# AUC3.net
KiCad netlist of a schematic drawn in Altium Designer
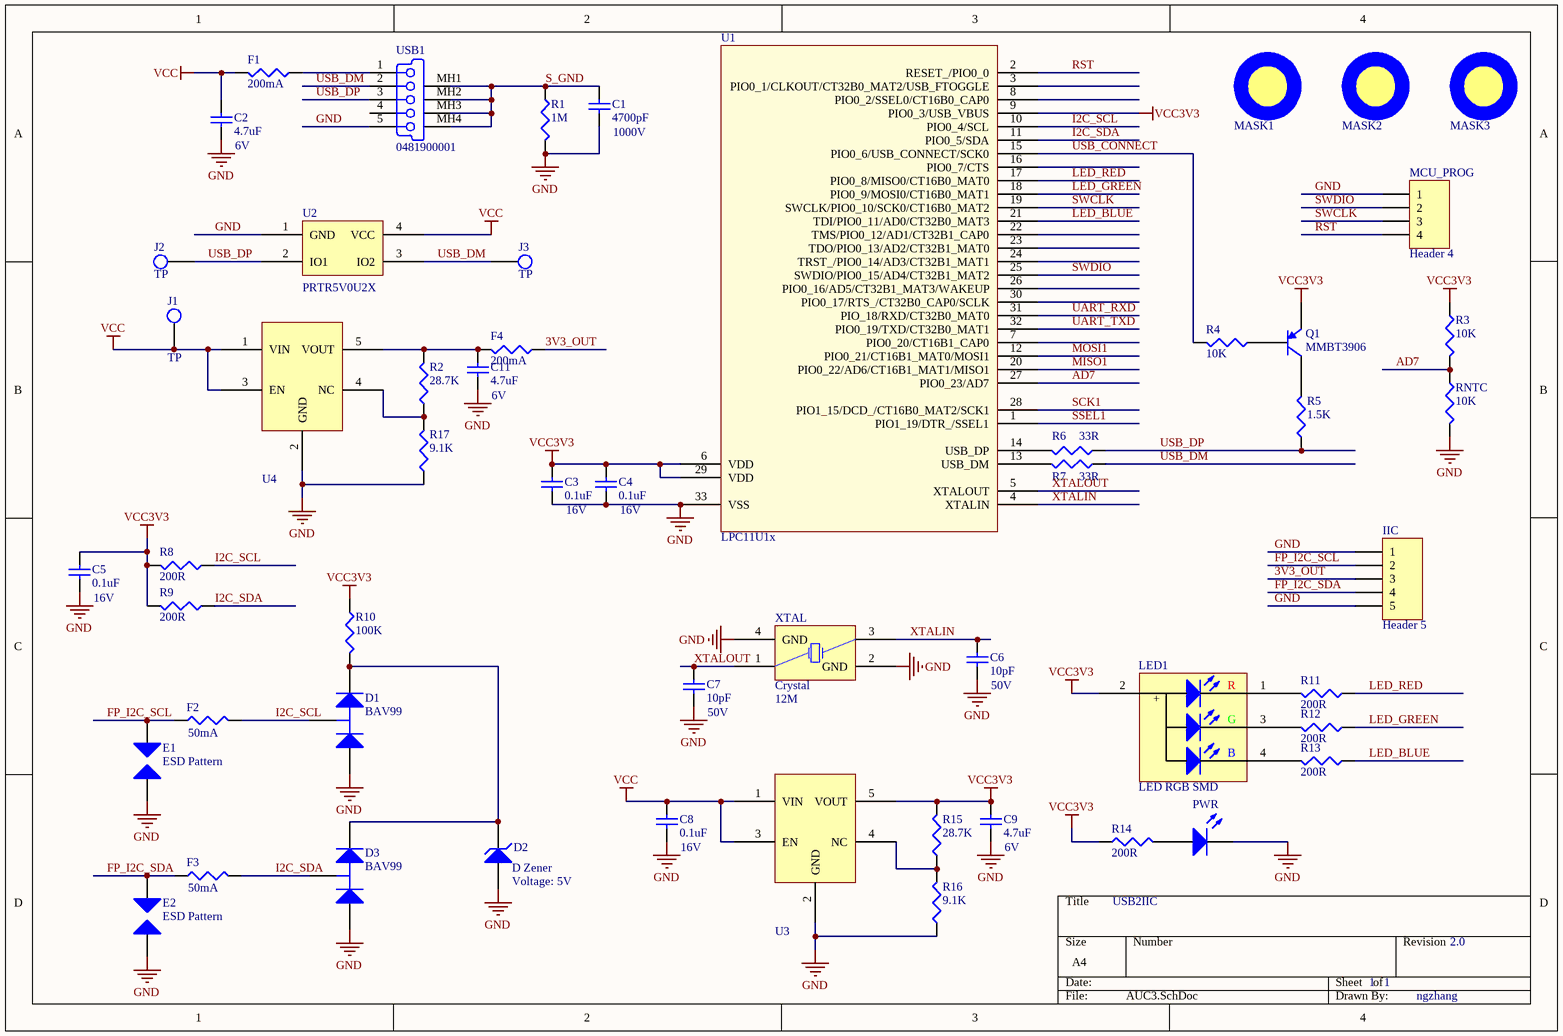
[diagram p0: AUC3.SchDoc]

(export (version "E")
  (design (tool "Eeschema 10.0.6"))
  (components
    (comp (ref "C1")
      (value "4700pF")
      (footprint "CAPC3216L")
      (description "Capacitor (Semiconductor SIM Model)")
      (fields (field (name "VOLTAGE") "1000V") (field (name "PUBLISHER") "Altium Limited"))
      (libsource (lib "avalon_all") (part "Cap Semi"))
    )
    (comp (ref "C2")
      (value "4.7uF")
      (footprint "CAPC1608L")
      (description "Capacitor (Semiconductor SIM Model)")
      (fields (field (name "VOLTAGE") "6V") (field (name "PUBLISHER") "Altium Limited"))
      (libsource (lib "Miscellaneous Devices") (part "Cap Semi"))
    )
    (comp (ref "C3")
      (value "0.1uF")
      (footprint "CAPC1005L")
      (description "Capacitor (Semiconductor SIM Model)")
      (fields (field (name "VOLTAGE") "16V") (field (name "PUBLISHER") "Altium Limited"))
      (libsource (lib "Miscellaneous Devices") (part "Cap Semi"))
    )
    (comp (ref "C4")
      (value "0.1uF")
      (footprint "CAPC1005L")
      (description "Capacitor (Semiconductor SIM Model)")
      (fields (field (name "VOLTAGE") "16V") (field (name "PUBLISHER") "Altium Limited"))
      (libsource (lib "Miscellaneous Devices") (part "Cap Semi"))
    )
    (comp (ref "C5")
      (value "0.1uF")
      (footprint "CAPC1005L")
      (description "Capacitor (Semiconductor SIM Model)")
      (fields (field (name "VOLTAGE") "16V") (field (name "PUBLISHER") "Altium Limited"))
      (libsource (lib "Miscellaneous Devices") (part "Cap Semi"))
    )
    (comp (ref "C6")
      (value "10pF")
      (footprint "CAPC1005L")
      (description "Capacitor (Semiconductor SIM Model)")
      (fields (field (name "VOLTAGE") "50V") (field (name "PUBLISHER") "Altium Limited"))
      (libsource (lib "Miscellaneous Devices") (part "Cap Semi"))
    )
    (comp (ref "C7")
      (value "10pF")
      (footprint "CAPC1005L")
      (description "Capacitor (Semiconductor SIM Model)")
      (fields (field (name "VOLTAGE") "50V") (field (name "PUBLISHER") "Altium Limited"))
      (libsource (lib "Miscellaneous Devices") (part "Cap Semi"))
    )
    (comp (ref "C8")
      (value "0.1uF")
      (footprint "CAPC1005L")
      (description "Capacitor (Semiconductor SIM Model)")
      (fields (field (name "VOLTAGE") "16V") (field (name "PUBLISHER") "Altium Limited"))
      (libsource (lib "Miscellaneous Devices") (part "Cap Semi"))
    )
    (comp (ref "C9")
      (value "4.7uF")
      (footprint "CAPC1608L")
      (description "Capacitor (Semiconductor SIM Model)")
      (fields (field (name "VOLTAGE") "6V") (field (name "PUBLISHER") "Altium Limited"))
      (libsource (lib "Miscellaneous Devices") (part "Cap Semi"))
    )
    (comp (ref "C11")
      (value "4.7uF")
      (footprint "CAPC1608L")
      (description "Capacitor (Semiconductor SIM Model)")
      (fields (field (name "VOLTAGE") "6V") (field (name "PUBLISHER") "Altium Limited"))
      (libsource (lib "Miscellaneous Devices") (part "Cap Semi"))
    )
    (comp (ref "D1")
      (value "BAV99")
      (footprint "SOT-23_L")
      (description "Silicon Switching Diode Array for High-Speed Switching")
      (fields (field (name "PUBLISHER") "Altium Limited"))
      (libsource (lib "Infineon Discrete Diode") (part "BAV99"))
    )
    (comp (ref "D2")
      (value "D Zener")
      (footprint "DO-214AC")
      (description "Zener Diode")
      (fields (field (name "VOLTAGE") "5V") (field (name "PUBLISHER") "Altium Limited"))
      (libsource (lib "Miscellaneous Devices") (part "D Zener"))
    )
    (comp (ref "D3")
      (value "BAV99")
      (footprint "SOT-23_L")
      (description "Silicon Switching Diode Array for High-Speed Switching")
      (fields (field (name "PUBLISHER") "Altium Limited"))
      (libsource (lib "Infineon Discrete Diode") (part "BAV99"))
    )
    (comp (ref "E1") (value "ESD Pattern") (footprint "ESD") (libsource (lib "avalon_all") (part "ESD")))
    (comp (ref "E2") (value "ESD Pattern") (footprint "ESD") (libsource (lib "avalon_all") (part "ESD")))
    (comp (ref "F1")
      (value "200mA")
      (footprint "RESC3216L")
      (description "Resistor")
      (fields (field (name "PUBLISHER") "Altium Limited"))
      (libsource (lib "avalon_all") (part "Res3"))
    )
    (comp (ref "F2")
      (value "50mA")
      (footprint "RESC2012l")
      (description "Resistor")
      (fields (field (name "PUBLISHER") "Altium Limited"))
      (libsource (lib "Miscellaneous Devices") (part "Res3"))
    )
    (comp (ref "F3")
      (value "50mA")
      (footprint "RESC2012l")
      (description "Resistor")
      (fields (field (name "PUBLISHER") "Altium Limited"))
      (libsource (lib "Miscellaneous Devices") (part "Res3"))
    )
    (comp (ref "F4")
      (value "200mA")
      (footprint "RESC3216L")
      (description "Resistor")
      (fields (field (name "PUBLISHER") "Altium Limited"))
      (libsource (lib "avalon_all") (part "Res3"))
    )
    (comp (ref "IIC")
      (value "Header 5")
      (footprint "HDR1X50-s")
      (description "Header, 5-Pin")
      (fields (field (name "PUBLISHER") "Altium Limited"))
      (libsource (lib "Miscellaneous Connectors") (part "Header 5"))
    )
    (comp (ref "J1")
      (value "TP")
      (footprint "tp")
      (fields (field (name "PUBLISHER") "Altium Limited"))
      (libsource (lib "A7.1") (part "TP"))
    )
    (comp (ref "J2")
      (value "TP")
      (footprint "tp")
      (fields (field (name "PUBLISHER") "Altium Limited"))
      (libsource (lib "A7.1") (part "TP"))
    )
    (comp (ref "J3")
      (value "TP")
      (footprint "tp")
      (fields (field (name "PUBLISHER") "Altium Limited"))
      (libsource (lib "A7.1") (part "TP"))
    )
    (comp (ref "LED1")
      (value "LED RGB SMD")
      (footprint "LED3528RGB")
      (libsource (lib "avalon_all") (part "LED3528RGB"))
    )
    (comp (ref "MASK1") (value "MASK") (footprint "MASK_L") (libsource (lib "avalon_all") (part "MASK")))
    (comp (ref "MASK2") (value "MASK") (footprint "MASK_L") (libsource (lib "avalon_all") (part "MASK")))
    (comp (ref "MASK3") (value "MASK") (footprint "MASKTEST") (libsource (lib "avalon_all") (part "MASK")))
    (comp (ref "MCU_PROG")
      (value "Header 4")
      (footprint "HDR1X4")
      (description "Header, 4-Pin")
      (fields (field (name "PUBLISHER") "Altium Limited"))
      (libsource (lib "Miscellaneous Connectors") (part "Header 4"))
    )
    (comp (ref "PWR")
      (value "LED3")
      (footprint "CD1608-0603")
      (description "Typical GREEN SiC LED")
      (fields (field (name "PUBLISHER") "Altium Limited"))
      (libsource (lib "avalon_all") (part "LED3"))
    )
    (comp (ref "Q1")
      (value "MMBT3906")
      (footprint "SOT23_N")
      (description "PNP Switching Transistor")
      (fields (field (name "PUBLISHER") "Altium Limited"))
      (libsource (lib "Philips Discrete BJT - Low Power") (part "MMBT3906"))
    )
    (comp (ref "R1")
      (value "1M")
      (footprint "RESC3216L")
      (description "Resistor")
      (fields (field (name "PUBLISHER") "Altium Limited"))
      (libsource (lib "avalon_all") (part "Res3"))
    )
    (comp (ref "R2")
      (value "28.7K")
      (footprint "RESC1005L")
      (description "Resistor")
      (fields (field (name "PUBLISHER") "Altium Limited"))
      (libsource (lib "avalon_all") (part "Res3"))
    )
    (comp (ref "R3")
      (value "10K")
      (footprint "RESC1005L")
      (description "Resistor")
      (fields (field (name "PUBLISHER") "Altium Limited"))
      (libsource (lib "avalon_all") (part "Res3"))
    )
    (comp (ref "R4")
      (value "10K")
      (footprint "RESC1005L")
      (description "Resistor")
      (fields (field (name "PUBLISHER") "Altium Limited"))
      (libsource (lib "avalon_all") (part "Res3"))
    )
    (comp (ref "R5")
      (value "1.5K")
      (footprint "RESC1005L")
      (description "Resistor")
      (fields (field (name "PUBLISHER") "Altium Limited"))
      (libsource (lib "avalon_all") (part "Res3"))
    )
    (comp (ref "R6")
      (value "33R")
      (footprint "RESC1005L")
      (description "Resistor")
      (fields (field (name "PUBLISHER") "Altium Limited"))
      (libsource (lib "avalon_all") (part "Res3"))
    )
    (comp (ref "R7")
      (value "33R")
      (footprint "RESC1005L")
      (description "Resistor")
      (fields (field (name "PUBLISHER") "Altium Limited"))
      (libsource (lib "avalon_all") (part "Res3"))
    )
    (comp (ref "R8")
      (value "200R")
      (footprint "RESC1005L")
      (description "Resistor")
      (fields (field (name "PUBLISHER") "Altium Limited"))
      (libsource (lib "avalon_all") (part "Res3"))
    )
    (comp (ref "R9")
      (value "200R")
      (footprint "RESC1005L")
      (description "Resistor")
      (fields (field (name "PUBLISHER") "Altium Limited"))
      (libsource (lib "avalon_all") (part "Res3"))
    )
    (comp (ref "R10")
      (value "100K")
      (footprint "RESC1005L")
      (description "Resistor")
      (fields (field (name "PUBLISHER") "Altium Limited"))
      (libsource (lib "avalon_all") (part "Res3"))
    )
    (comp (ref "R11")
      (value "200R")
      (footprint "RESC1005L")
      (description "Resistor")
      (fields (field (name "PUBLISHER") "Altium Limited"))
      (libsource (lib "avalon_all") (part "Res3"))
    )
    (comp (ref "R12")
      (value "200R")
      (footprint "RESC1005L")
      (description "Resistor")
      (fields (field (name "PUBLISHER") "Altium Limited"))
      (libsource (lib "avalon_all") (part "Res3"))
    )
    (comp (ref "R13")
      (value "200R")
      (footprint "RESC1005L")
      (description "Resistor")
      (fields (field (name "PUBLISHER") "Altium Limited"))
      (libsource (lib "avalon_all") (part "Res3"))
    )
    (comp (ref "R14")
      (value "200R")
      (footprint "RESC1005L")
      (description "Resistor")
      (fields (field (name "PUBLISHER") "Altium Limited"))
      (libsource (lib "avalon_all") (part "Res3"))
    )
    (comp (ref "R15")
      (value "28.7K")
      (footprint "RESC1005L")
      (description "Resistor")
      (fields (field (name "PUBLISHER") "Altium Limited"))
      (libsource (lib "avalon_all") (part "Res3"))
    )
    (comp (ref "R16")
      (value "9.1K")
      (footprint "RESC1005L")
      (description "Resistor")
      (fields (field (name "PUBLISHER") "Altium Limited"))
      (libsource (lib "avalon_all") (part "Res3"))
    )
    (comp (ref "R17")
      (value "9.1K")
      (footprint "RESC1005L")
      (description "Resistor")
      (fields (field (name "PUBLISHER") "Altium Limited"))
      (libsource (lib "avalon_all") (part "Res3"))
    )
    (comp (ref "RNTC")
      (value "10K")
      (footprint "RESC1608L")
      (description "Resistor")
      (fields (field (name "PUBLISHER") "Altium Limited"))
      (libsource (lib "avalon_all") (part "Res3"))
    )
    (comp (ref "U1")
      (value "LPC11U1x")
      (footprint "HVQFN33")
      (description "32-bit ARM Cortex-M0 microcontroller")
      (libsource (lib "avalon_all") (part "LPC11U1x"))
    )
    (comp (ref "U2")
      (value "PRTR5V0U2X")
      (footprint "SOT143B_L")
      (description "Ultra low capacitance double rail-to-rail ESD protection diode")
      (libsource (lib "avalon_all") (part "PRTR5V0U2X"))
    )
    (comp (ref "U3")
      (value "LDO")
      (footprint "SOT23-5AL")
      (description "600mA, Ultra-Low Dropout, CMOS Regulatorout Bypass Capacitor CMOS LDO Regulator")
      (libsource (lib "avalon_all") (part "RT9187C"))
    )
    (comp (ref "U4")
      (value "LDO")
      (footprint "SOT23-5AL")
      (description "600mA, Ultra-Low Dropout, CMOS Regulatorout Bypass Capacitor CMOS LDO Regulator")
      (libsource (lib "avalon_all") (part "RT9187C"))
    )
    (comp (ref "USB1")
      (value "0481900001")
      (footprint "USB_Micro_B2")
      (fields (field (name "PUBLISHER") "Altium Limited"))
      (libsource (lib "Molex Serial Bus Mini USB") (part "0481900001"))
    )
    (comp (ref "XTAL")
      (value "Crystal")
      (footprint "XO2520")
      (fields (field (name "ALTIUM_VALUE") "12M"))
      (libsource (lib "avalon_all") (part "Crystal SMD"))
    )
  )
  (nets
    (net (code "1") (name "/3V3_OUT") (class "Default")
      (node (ref "F4") (pin "1") (pinfunction "1_1") (pintype "passive"))
      (node (ref "IIC") (pin "3") (pinfunction "3_3") (pintype "passive"))
    )
    (net (code "2") (name "/AD7") (class "Default")
      (node (ref "R3") (pin "2") (pinfunction "2_2") (pintype "passive"))
      (node (ref "RNTC") (pin "1") (pinfunction "1_1") (pintype "passive"))
      (node (ref "U1") (pin "27") (pinfunction "PIO0_23/AD7_27") (pintype "passive"))
    )
    (net (code "3") (name "/FP_I2C_SCL") (class "Default")
      (node (ref "E1") (pin "2") (pinfunction "2_2") (pintype "passive"))
      (node (ref "F2") (pin "1") (pinfunction "1_1") (pintype "passive"))
      (node (ref "IIC") (pin "2") (pinfunction "2_2") (pintype "passive"))
    )
    (net (code "4") (name "/FP_I2C_SDA") (class "Default")
      (node (ref "E2") (pin "2") (pinfunction "2_2") (pintype "passive"))
      (node (ref "F3") (pin "1") (pinfunction "1_1") (pintype "passive"))
      (node (ref "IIC") (pin "4") (pinfunction "4_4") (pintype "passive"))
    )
    (net (code "5") (name "/I2C_SCL") (class "Default")
      (node (ref "D1") (pin "3") (pinfunction "C_3") (pintype "passive"))
      (node (ref "F2") (pin "2") (pinfunction "2_2") (pintype "passive"))
      (node (ref "R8") (pin "1") (pinfunction "1_1") (pintype "passive"))
      (node (ref "U1") (pin "10") (pinfunction "PIO0_4/SCL_10") (pintype "passive"))
    )
    (net (code "6") (name "/I2C_SDA") (class "Default")
      (node (ref "D3") (pin "3") (pinfunction "C_3") (pintype "passive"))
      (node (ref "F3") (pin "2") (pinfunction "2_2") (pintype "passive"))
      (node (ref "R9") (pin "1") (pinfunction "1_1") (pintype "passive"))
      (node (ref "U1") (pin "11") (pinfunction "PIO0_5/SDA_11") (pintype "passive"))
    )
    (net (code "7") (name "/LED_BLUE") (class "Default")
      (node (ref "R13") (pin "1") (pinfunction "1_1") (pintype "passive"))
      (node (ref "U1") (pin "21") (pinfunction "TDI/PIO0_11/AD0/CT32B0_MAT3_21") (pintype "passive"))
    )
    (net (code "8") (name "/LED_GREEN") (class "Default")
      (node (ref "R12") (pin "1") (pinfunction "1_1") (pintype "passive"))
      (node (ref "U1") (pin "18") (pinfunction "PIO0_9/MOSI0/CT16B0_MAT1_18") (pintype "passive"))
    )
    (net (code "9") (name "/LED_RED") (class "Default")
      (node (ref "R11") (pin "1") (pinfunction "1_1") (pintype "passive"))
      (node (ref "U1") (pin "17") (pinfunction "PIO0_8/MISO0/CT16B0_MAT0_17") (pintype "passive"))
    )
    (net (code "10") (name "/MISO1") (class "Default")
      (node (ref "U1") (pin "20") (pinfunction "PIO0_22/AD6/CT16B1_MAT1/MISO1_20") (pintype "passive"))
    )
    (net (code "11") (name "/MOSI1") (class "Default")
      (node (ref "U1") (pin "12") (pinfunction "PIO0_21/CT16B1_MAT0/MOSI1_12") (pintype "passive"))
    )
    (net (code "12") (name "/RST") (class "Default")
      (node (ref "MCU_PROG") (pin "4") (pinfunction "4_4") (pintype "passive"))
      (node (ref "U1") (pin "2") (pinfunction "RESET_/PIO0_0_2") (pintype "passive"))
    )
    (net (code "13") (name "/SCK1") (class "Default")
      (node (ref "U1") (pin "28") (pinfunction "PIO1_15/DCD_/CT16B0_MAT2/SCK1_28") (pintype "passive"))
    )
    (net (code "14") (name "/SSEL1") (class "Default")
      (node (ref "U1") (pin "1") (pinfunction "PIO1_19/DTR_/SSEL1_1") (pintype "passive"))
    )
    (net (code "15") (name "/SWCLK") (class "Default")
      (node (ref "MCU_PROG") (pin "3") (pinfunction "3_3") (pintype "passive"))
      (node (ref "U1") (pin "19") (pinfunction "SWCLK/PIO0_10/SCK0/CT16B0_MAT2_19") (pintype "passive"))
    )
    (net (code "16") (name "/SWDIO") (class "Default")
      (node (ref "MCU_PROG") (pin "2") (pinfunction "2_2") (pintype "passive"))
      (node (ref "U1") (pin "25") (pinfunction "SWDIO/PIO0_15/AD4/CT32B1_MAT2_25") (pintype "passive"))
    )
    (net (code "17") (name "/S_GND") (class "Default")
      (node (ref "C1") (pin "2") (pinfunction "2_2") (pintype "passive"))
      (node (ref "R1") (pin "1") (pinfunction "1_1") (pintype "passive"))
      (node (ref "USB1") (pin "MH1") (pinfunction "Tab_MH1") (pintype "passive"))
      (node (ref "USB1") (pin "MH2") (pinfunction "Tab_MH2") (pintype "passive"))
      (node (ref "USB1") (pin "MH3") (pinfunction "Tab_MH3") (pintype "passive"))
      (node (ref "USB1") (pin "MH4") (pinfunction "Tab_MH4") (pintype "passive"))
    )
    (net (code "18") (name "/UART_RXD") (class "Default")
      (node (ref "U1") (pin "31") (pinfunction "PIO_18/RXD/CT32B0_MAT0_31") (pintype "passive"))
    )
    (net (code "19") (name "/UART_TXD") (class "Default")
      (node (ref "U1") (pin "32") (pinfunction "PIO0_19/TXD/CT32B0_MAT1_32") (pintype "passive"))
    )
    (net (code "20") (name "/USB_CONNECT") (class "Default")
      (node (ref "R4") (pin "2") (pinfunction "2_2") (pintype "passive"))
      (node (ref "U1") (pin "15") (pinfunction "PIO0_6/USB_CONNECT/SCK0_15") (pintype "passive"))
    )
    (net (code "21") (name "/USB_DM") (class "Default")
      (node (ref "J3") (pin "1") (pinfunction "1_1") (pintype "passive"))
      (node (ref "R7") (pin "1") (pinfunction "1_1") (pintype "passive"))
      (node (ref "U2") (pin "3") (pinfunction "IO2_3") (pintype "power_in"))
      (node (ref "USB1") (pin "2") (pinfunction "D-_2") (pintype "passive"))
    )
    (net (code "22") (name "/USB_DP") (class "Default")
      (node (ref "J2") (pin "1") (pinfunction "1_1") (pintype "passive"))
      (node (ref "R5") (pin "1") (pinfunction "1_1") (pintype "passive"))
      (node (ref "R6") (pin "1") (pinfunction "1_1") (pintype "passive"))
      (node (ref "U2") (pin "2") (pinfunction "IO1_2") (pintype "power_in"))
      (node (ref "USB1") (pin "3") (pinfunction "D+_3") (pintype "passive"))
    )
    (net (code "23") (name "/XTALIN") (class "Default")
      (node (ref "C6") (pin "1") (pinfunction "1_1") (pintype "passive"))
      (node (ref "U1") (pin "4") (pinfunction "XTALIN_4") (pintype "passive"))
      (node (ref "XTAL") (pin "3") (pinfunction "OSC2_3") (pintype "passive"))
    )
    (net (code "24") (name "/XTALOUT") (class "Default")
      (node (ref "C7") (pin "1") (pinfunction "1_1") (pintype "passive"))
      (node (ref "U1") (pin "5") (pinfunction "XTALOUT_5") (pintype "passive"))
      (node (ref "XTAL") (pin "1") (pinfunction "OSC1_1") (pintype "passive"))
    )
    (net (code "25") (name "GND") (class "Default")
      (node (ref "C1") (pin "1") (pinfunction "1_1") (pintype "passive"))
      (node (ref "C11") (pin "2") (pinfunction "2_2") (pintype "passive"))
      (node (ref "C2") (pin "2") (pinfunction "2_2") (pintype "passive"))
      (node (ref "C3") (pin "2") (pinfunction "2_2") (pintype "passive"))
      (node (ref "C4") (pin "2") (pinfunction "2_2") (pintype "passive"))
      (node (ref "C5") (pin "2") (pinfunction "2_2") (pintype "passive"))
      (node (ref "C6") (pin "2") (pinfunction "2_2") (pintype "passive"))
      (node (ref "C7") (pin "2") (pinfunction "2_2") (pintype "passive"))
      (node (ref "C8") (pin "2") (pinfunction "2_2") (pintype "passive"))
      (node (ref "C9") (pin "2") (pinfunction "2_2") (pintype "passive"))
      (node (ref "D1") (pin "1") (pinfunction "A_1") (pintype "passive"))
      (node (ref "D2") (pin "1") (pinfunction "A_1") (pintype "passive"))
      (node (ref "D3") (pin "1") (pinfunction "A_1") (pintype "passive"))
      (node (ref "E1") (pin "1") (pinfunction "1_1") (pintype "passive"))
      (node (ref "E2") (pin "1") (pinfunction "1_1") (pintype "passive"))
      (node (ref "IIC") (pin "1") (pinfunction "1_1") (pintype "passive"))
      (node (ref "IIC") (pin "5") (pinfunction "5_5") (pintype "passive"))
      (node (ref "MCU_PROG") (pin "1") (pinfunction "1_1") (pintype "passive"))
      (node (ref "PWR") (pin "2") (pinfunction "K_2") (pintype "passive"))
      (node (ref "R1") (pin "2") (pinfunction "2_2") (pintype "passive"))
      (node (ref "R16") (pin "1") (pinfunction "1_1") (pintype "passive"))
      (node (ref "R17") (pin "1") (pinfunction "1_1") (pintype "passive"))
      (node (ref "RNTC") (pin "2") (pinfunction "2_2") (pintype "passive"))
      (node (ref "U1") (pin "33") (pinfunction "VSS_33") (pintype "passive"))
      (node (ref "U2") (pin "1") (pinfunction "GND_1") (pintype "power_in"))
      (node (ref "U3") (pin "2") (pinfunction "GND_2") (pintype "passive"))
      (node (ref "U4") (pin "2") (pinfunction "GND_2") (pintype "passive"))
      (node (ref "USB1") (pin "5") (pinfunction "GND_5") (pintype "passive"))
      (node (ref "XTAL") (pin "2") (pinfunction "GND_2") (pintype "passive"))
      (node (ref "XTAL") (pin "4") (pinfunction "GND_4") (pintype "passive"))
    )
    (net (code "26") (name "Net-(D1-K)") (class "Default")
      (node (ref "D1") (pin "2") (pinfunction "K_2") (pintype "passive"))
      (node (ref "D2") (pin "2") (pinfunction "K_2") (pintype "passive"))
      (node (ref "D3") (pin "2") (pinfunction "K_2") (pintype "passive"))
      (node (ref "R10") (pin "2") (pinfunction "2_2") (pintype "passive"))
    )
    (net (code "27") (name "Net-(LED1-B)") (class "Default")
      (node (ref "LED1") (pin "4") (pinfunction "B_4") (pintype "passive"))
      (node (ref "R13") (pin "2") (pinfunction "2_2") (pintype "passive"))
    )
    (net (code "28") (name "Net-(LED1-G)") (class "Default")
      (node (ref "LED1") (pin "3") (pinfunction "G_3") (pintype "passive"))
      (node (ref "R12") (pin "2") (pinfunction "2_2") (pintype "passive"))
    )
    (net (code "29") (name "Net-(LED1-R)") (class "Default")
      (node (ref "LED1") (pin "1") (pinfunction "R_1") (pintype "passive"))
      (node (ref "R11") (pin "2") (pinfunction "2_2") (pintype "passive"))
    )
    (net (code "30") (name "Net-(PWR-A)") (class "Default")
      (node (ref "PWR") (pin "1") (pinfunction "A_1") (pintype "passive"))
      (node (ref "R14") (pin "2") (pinfunction "2_2") (pintype "passive"))
    )
    (net (code "31") (name "Net-(Q1-B)") (class "Default")
      (node (ref "Q1") (pin "1") (pinfunction "B_1") (pintype "passive"))
      (node (ref "R4") (pin "1") (pinfunction "1_1") (pintype "passive"))
    )
    (net (code "32") (name "Net-(Q1-C)") (class "Default")
      (node (ref "Q1") (pin "3") (pinfunction "C_3") (pintype "passive"))
      (node (ref "R5") (pin "2") (pinfunction "2_2") (pintype "passive"))
    )
    (net (code "33") (name "Net-(U1-USB_DM)") (class "Default")
      (node (ref "R7") (pin "2") (pinfunction "2_2") (pintype "passive"))
      (node (ref "U1") (pin "13") (pinfunction "USB_DM_13") (pintype "passive"))
    )
    (net (code "34") (name "Net-(U1-USB_DP)") (class "Default")
      (node (ref "R6") (pin "2") (pinfunction "2_2") (pintype "passive"))
      (node (ref "U1") (pin "14") (pinfunction "USB_DP_14") (pintype "passive"))
    )
    (net (code "35") (name "Net-(U3-NC)") (class "Default")
      (node (ref "R15") (pin "1") (pinfunction "1_1") (pintype "passive"))
      (node (ref "R16") (pin "2") (pinfunction "2_2") (pintype "passive"))
      (node (ref "U3") (pin "4") (pinfunction "NC_4") (pintype "passive"))
    )
    (net (code "36") (name "Net-(U4-NC)") (class "Default")
      (node (ref "R17") (pin "2") (pinfunction "2_2") (pintype "passive"))
      (node (ref "R2") (pin "1") (pinfunction "1_1") (pintype "passive"))
      (node (ref "U4") (pin "4") (pinfunction "NC_4") (pintype "passive"))
    )
    (net (code "37") (name "Net-(U4-VOUT)") (class "Default")
      (node (ref "C11") (pin "1") (pinfunction "1_1") (pintype "passive"))
      (node (ref "F4") (pin "2") (pinfunction "2_2") (pintype "passive"))
      (node (ref "R2") (pin "2") (pinfunction "2_2") (pintype "passive"))
      (node (ref "U4") (pin "5") (pinfunction "VOUT_5") (pintype "passive"))
    )
    (net (code "38") (name "Net-(USB1-V_BUS_(5V))") (class "Default")
      (node (ref "F1") (pin "1") (pinfunction "1_1") (pintype "passive"))
      (node (ref "USB1") (pin "1") (pinfunction "V_BUS_(5V)_1") (pintype "passive"))
    )
    (net (code "39") (name "VCC") (class "Default")
      (node (ref "C2") (pin "1") (pinfunction "1_1") (pintype "passive"))
      (node (ref "C8") (pin "1") (pinfunction "1_1") (pintype "passive"))
      (node (ref "F1") (pin "2") (pinfunction "2_2") (pintype "passive"))
      (node (ref "J1") (pin "1") (pinfunction "1_1") (pintype "passive"))
      (node (ref "U2") (pin "4") (pinfunction "VCC_4") (pintype "power_in"))
      (node (ref "U3") (pin "1") (pinfunction "VIN_1") (pintype "passive"))
      (node (ref "U3") (pin "3") (pinfunction "EN_3") (pintype "passive"))
      (node (ref "U4") (pin "1") (pinfunction "VIN_1") (pintype "passive"))
      (node (ref "U4") (pin "3") (pinfunction "EN_3") (pintype "passive"))
    )
    (net (code "40") (name "VCC3V3") (class "Default")
      (node (ref "C3") (pin "1") (pinfunction "1_1") (pintype "passive"))
      (node (ref "C4") (pin "1") (pinfunction "1_1") (pintype "passive"))
      (node (ref "C5") (pin "1") (pinfunction "1_1") (pintype "passive"))
      (node (ref "C9") (pin "1") (pinfunction "1_1") (pintype "passive"))
      (node (ref "LED1") (pin "2") (pinfunction "COM+_2") (pintype "passive"))
      (node (ref "Q1") (pin "2") (pinfunction "E_2") (pintype "passive"))
      (node (ref "R10") (pin "1") (pinfunction "1_1") (pintype "passive"))
      (node (ref "R14") (pin "1") (pinfunction "1_1") (pintype "passive"))
      (node (ref "R15") (pin "2") (pinfunction "2_2") (pintype "passive"))
      (node (ref "R3") (pin "1") (pinfunction "1_1") (pintype "passive"))
      (node (ref "R8") (pin "2") (pinfunction "2_2") (pintype "passive"))
      (node (ref "R9") (pin "2") (pinfunction "2_2") (pintype "passive"))
      (node (ref "U1") (pin "29") (pinfunction "VDD_29") (pintype "passive"))
      (node (ref "U1") (pin "6") (pinfunction "VDD_6") (pintype "passive"))
      (node (ref "U1") (pin "9") (pinfunction "PIO0_3/USB_VBUS_9") (pintype "passive"))
      (node (ref "U3") (pin "5") (pinfunction "VOUT_5") (pintype "passive"))
    )
    (net (code "41") (name "unconnected-(U1-PIO0_1{slash}CLKOUT{slash}CT32B0_MAT2{slash}USB_FTOGGLE-Pad3)") (class "Default")
      (node (ref "U1") (pin "3") (pinfunction "PIO0_1/CLKOUT/CT32B0_MAT2/USB_FTOGGLE_3") (pintype "passive"))
    )
    (net (code "42") (name "unconnected-(U1-PIO0_2{slash}SSEL0{slash}CT16B0_CAP0-Pad8)") (class "Default")
      (node (ref "U1") (pin "8") (pinfunction "PIO0_2/SSEL0/CT16B0_CAP0_8") (pintype "passive"))
    )
    (net (code "43") (name "unconnected-(U1-PIO0_7{slash}CTS-Pad16)") (class "Default")
      (node (ref "U1") (pin "16") (pinfunction "PIO0_7/CTS_16") (pintype "passive"))
    )
    (net (code "44") (name "unconnected-(U1-PIO0_16{slash}AD5{slash}CT32B1_MAT3{slash}WAKEUP-Pad26)") (class "Default")
      (node (ref "U1") (pin "26") (pinfunction "PIO0_16/AD5/CT32B1_MAT3/WAKEUP_26") (pintype "passive"))
    )
    (net (code "45") (name "unconnected-(U1-PIO0_17{slash}RTS_{slash}CT32B0_CAP0{slash}SCLK-Pad30)") (class "Default")
      (node (ref "U1") (pin "30") (pinfunction "PIO0_17/RTS_/CT32B0_CAP0/SCLK_30") (pintype "passive"))
    )
    (net (code "46") (name "unconnected-(U1-PIO0_20{slash}CT16B1_CAP0-Pad7)") (class "Default")
      (node (ref "U1") (pin "7") (pinfunction "PIO0_20/CT16B1_CAP0_7") (pintype "passive"))
    )
    (net (code "47") (name "unconnected-(U1-TDO{slash}PIO0_13{slash}AD2{slash}CT32B1_MAT0-Pad23)") (class "Default")
      (node (ref "U1") (pin "23") (pinfunction "TDO/PIO0_13/AD2/CT32B1_MAT0_23") (pintype "passive"))
    )
    (net (code "48") (name "unconnected-(U1-TMS{slash}PIO0_12{slash}AD1{slash}CT32B1_CAP0-Pad22)") (class "Default")
      (node (ref "U1") (pin "22") (pinfunction "TMS/PIO0_12/AD1/CT32B1_CAP0_22") (pintype "passive"))
    )
    (net (code "49") (name "unconnected-(U1-TRST_{slash}PIO0_14{slash}AD3{slash}CT32B1_MAT1-Pad24)") (class "Default")
      (node (ref "U1") (pin "24") (pinfunction "TRST_/PIO0_14/AD3/CT32B1_MAT1_24") (pintype "passive"))
    )
    (net (code "50") (name "unconnected-(USB1-NC-Pad4)") (class "Default")
      (node (ref "USB1") (pin "4") (pinfunction "NC_4") (pintype "passive"))
    )
  )
)
